# finacbv1.net
KiCad netlist of a schematic drawn in EAGLE
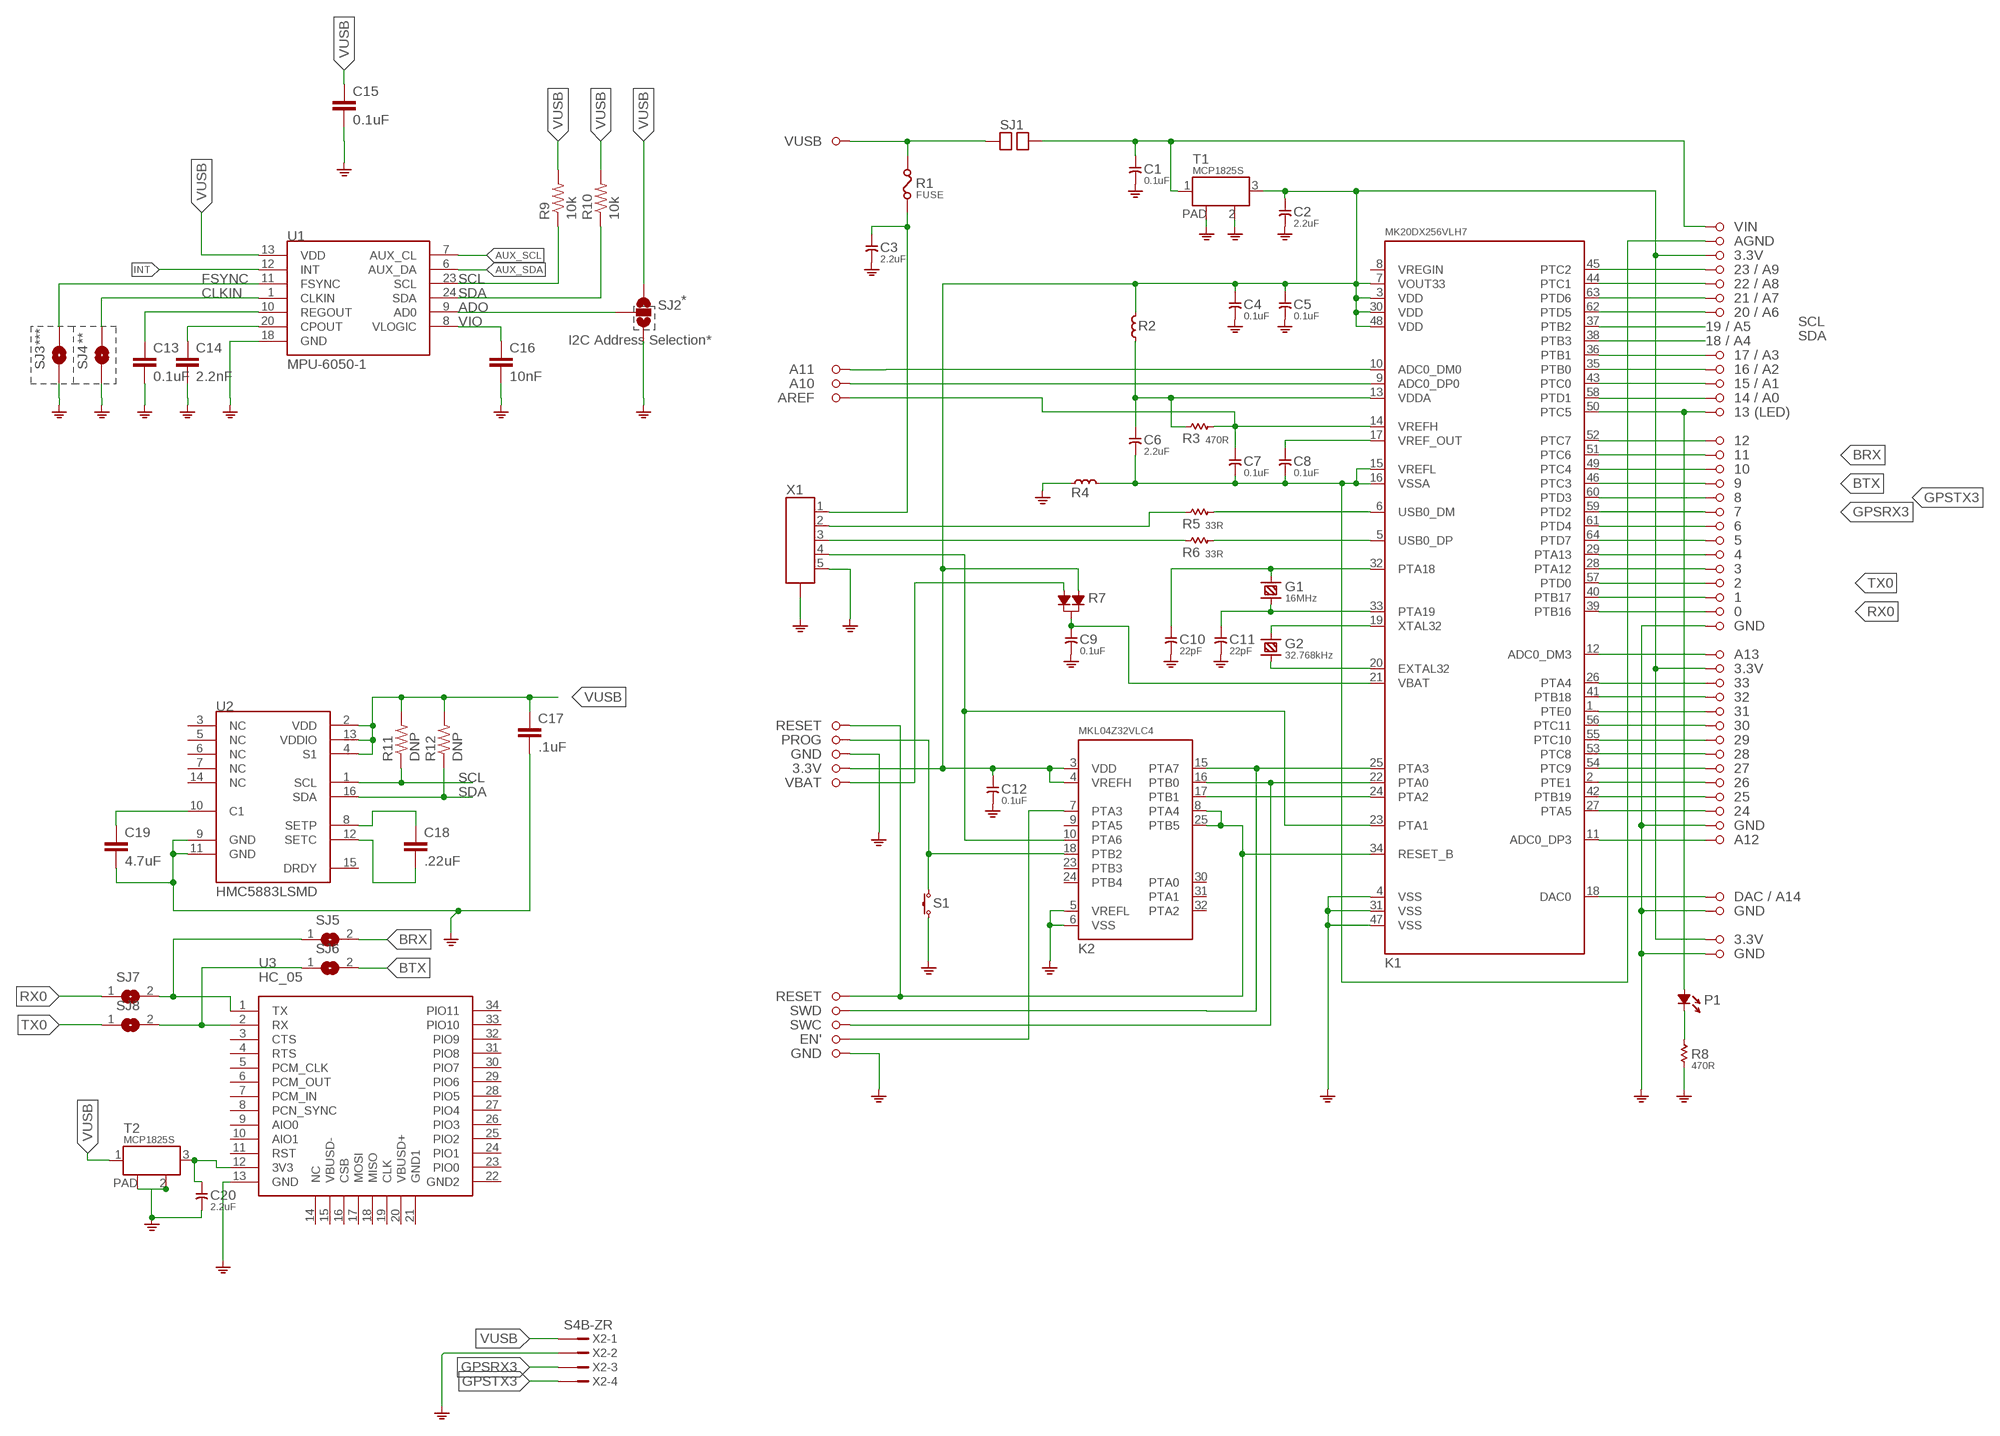
[diagram p0: schematic, sheet 1]

(export (version "E")
  (design (tool "Eeschema 10.0.6"))
  (components
    (comp (ref "C1")
      (value "0.1uF")
      (footprint "eagle-import:C0603")
      (fields (field (name "MF") "Murata Electronics") (field (name "MPN") "GRM188R71C104KA01D"))
      (libsource (lib "eagle-import") (part "CAPACITOR-0.1UF"))
    )
    (comp (ref "C2")
      (value "2.2uF")
      (footprint "eagle-import:C0805")
      (fields (field (name "MF") "Taiyo Yuden") (field (name "MPN") "TMK212B7225KG-TR"))
      (libsource (lib "eagle-import") (part "CAPACITOR-2.2UF"))
    )
    (comp (ref "C3")
      (value "2.2uF")
      (footprint "eagle-import:C0805")
      (fields (field (name "MF") "Taiyo Yuden") (field (name "MPN") "TMK212B7225KG-TR"))
      (libsource (lib "eagle-import") (part "CAPACITOR-2.2UF"))
    )
    (comp (ref "C4")
      (value "0.1uF")
      (footprint "eagle-import:C0603")
      (fields (field (name "MF") "Murata Electronics") (field (name "MPN") "GRM188R71C104KA01D"))
      (libsource (lib "eagle-import") (part "CAPACITOR-0.1UF"))
    )
    (comp (ref "C5")
      (value "0.1uF")
      (footprint "eagle-import:C0603")
      (fields (field (name "MF") "Murata Electronics") (field (name "MPN") "GRM188R71C104KA01D"))
      (libsource (lib "eagle-import") (part "CAPACITOR-0.1UF"))
    )
    (comp (ref "C6")
      (value "2.2uF")
      (footprint "eagle-import:C0805")
      (fields (field (name "MF") "Taiyo Yuden") (field (name "MPN") "TMK212B7225KG-TR"))
      (libsource (lib "eagle-import") (part "CAPACITOR-2.2UF"))
    )
    (comp (ref "C7")
      (value "0.1uF")
      (footprint "eagle-import:C0603")
      (fields (field (name "MF") "Murata Electronics") (field (name "MPN") "GRM188R71C104KA01D"))
      (libsource (lib "eagle-import") (part "CAPACITOR-0.1UF"))
    )
    (comp (ref "C8")
      (value "0.1uF")
      (footprint "eagle-import:C0603")
      (fields (field (name "MF") "Murata Electronics") (field (name "MPN") "GRM188R71C104KA01D"))
      (libsource (lib "eagle-import") (part "CAPACITOR-0.1UF"))
    )
    (comp (ref "C9")
      (value "0.1uF")
      (footprint "eagle-import:C0603")
      (fields (field (name "MF") "Murata Electronics") (field (name "MPN") "GRM188R71C104KA01D"))
      (libsource (lib "eagle-import") (part "CAPACITOR-0.1UF"))
    )
    (comp (ref "C10")
      (value "22pF")
      (footprint "eagle-import:C0603")
      (fields (field (name "MF") "Vishay / Vitramon") (field (name "MPN") "VJ0603A220JXACW1BC"))
      (libsource (lib "eagle-import") (part "CAPACITOR-22PF"))
    )
    (comp (ref "C11")
      (value "22pF")
      (footprint "eagle-import:C0603")
      (fields (field (name "MF") "Vishay / Vitramon") (field (name "MPN") "VJ0603A220JXACW1BC"))
      (libsource (lib "eagle-import") (part "CAPACITOR-22PF"))
    )
    (comp (ref "C12")
      (value "0.1uF")
      (footprint "eagle-import:C0603")
      (fields (field (name "MF") "Murata Electronics") (field (name "MPN") "GRM188R71C104KA01D"))
      (libsource (lib "eagle-import") (part "CAPACITOR-0.1UF"))
    )
    (comp (ref "C13")
      (value "0.1uF")
      (footprint "eagle-import:0603-CAP")
      (libsource (lib "eagle-import") (part "CAP0603-CAP"))
    )
    (comp (ref "C14")
      (value "2.2nF")
      (footprint "eagle-import:0603-CAP")
      (libsource (lib "eagle-import") (part "CAP0603-CAP"))
    )
    (comp (ref "C15")
      (value "0.1uF")
      (footprint "eagle-import:0603-CAP")
      (libsource (lib "eagle-import") (part "CAP0603-CAP"))
    )
    (comp (ref "C16")
      (value "10nF")
      (footprint "eagle-import:0603-CAP")
      (libsource (lib "eagle-import") (part "CAP0603-CAP"))
    )
    (comp (ref "C17")
      (value ".1uF")
      (footprint "eagle-import:0402-CAP")
      (libsource (lib "eagle-import") (part "CAP0402-CAP"))
    )
    (comp (ref "C18")
      (value ".22uF")
      (footprint "eagle-import:0402-CAP")
      (libsource (lib "eagle-import") (part "CAP0402-CAP"))
    )
    (comp (ref "C19")
      (value "4.7uF")
      (footprint "eagle-import:0402-CAP")
      (libsource (lib "eagle-import") (part "CAP0402-CAP"))
    )
    (comp (ref "C20")
      (value "2.2uF")
      (footprint "eagle-import:C0805")
      (fields (field (name "MF") "Taiyo Yuden") (field (name "MPN") "TMK212B7225KG-TR"))
      (libsource (lib "eagle-import") (part "CAPACITOR-2.2UF"))
    )
    (comp (ref "G1")
      (value "16MHz")
      (footprint "eagle-import:HC49US")
      (fields (field (name "MF") "ABRACON") (field (name "MPN") "ABL-16.000MHz-B1U"))
      (libsource (lib "eagle-import") (part "CRYSTAL-HC49US"))
    )
    (comp (ref "G2")
      (value "32.768kHz")
      (footprint "eagle-import:TC26H")
      (fields (field (name "MF") "Citizen FineDevice") (field (name "MPN") " CFS206-32.768KDZF-UB"))
      (libsource (lib "eagle-import") (part "CRYSTAL-TC26H"))
    )
    (comp (ref "K1")
      (value "MK20DX256VLH7")
      (footprint "eagle-import:LQFP64-05")
      (fields (field (name "MF") "NXP"))
      (libsource (lib "eagle-import") (part "MK20DX256VLH7"))
    )
    (comp (ref "K2")
      (value "MKL04Z32VLC4")
      (footprint "eagle-import:LQFP32-08")
      (fields (field (name "MF") "PJRC") (field (name "MPN") "IC_MKL04Z32_TQFP32"))
      (libsource (lib "eagle-import") (part "MKL04Z32VLC4"))
    )
    (comp (ref "P1")
      (value "LED")
      (footprint "eagle-import:LED-0805")
      (fields (field (name "MF") "ROHM Semiconductor") (field (name "MPN") "SML-211DTT86"))
      (libsource (lib "eagle-import") (part "LED"))
    )
    (comp (ref "R1")
      (value "FUSE")
      (footprint "eagle-import:F0805")
      (fields (field (name "MF") "Bel Fuse") (field (name "MPN") "0ZCK0050FF2E"))
      (libsource (lib "eagle-import") (part "FUSE"))
    )
    (comp (ref "R2")
      (value "FERRITE")
      (footprint "eagle-import:L0603")
      (fields (field (name "MF") "Murata Electronics") (field (name "MPN") " BLM18AG601SN1D"))
      (libsource (lib "eagle-import") (part "FERRITE"))
    )
    (comp (ref "R3")
      (value "470R")
      (footprint "eagle-import:R0603")
      (fields (field (name "MF") "Vishay") (field (name "MPN") "CRCW0603470RFKEA"))
      (libsource (lib "eagle-import") (part "RESISTOR-470R"))
    )
    (comp (ref "R4")
      (value "FERRITE")
      (footprint "eagle-import:L0603")
      (fields (field (name "MF") "Murata Electronics") (field (name "MPN") " BLM18AG601SN1D"))
      (libsource (lib "eagle-import") (part "FERRITE"))
    )
    (comp (ref "R5")
      (value "33R")
      (footprint "eagle-import:R0603")
      (fields (field (name "MF") "Panasonic") (field (name "MPN") "ERJ-PA3F33R0V"))
      (libsource (lib "eagle-import") (part "RESISTOR-33R"))
    )
    (comp (ref "R6")
      (value "33R")
      (footprint "eagle-import:R0603")
      (fields (field (name "MF") "Panasonic") (field (name "MPN") "ERJ-PA3F33R0V"))
      (libsource (lib "eagle-import") (part "RESISTOR-33R"))
    )
    (comp (ref "R7")
      (value "DIODE_DUAL")
      (footprint "eagle-import:SOT-23")
      (fields (field (name "MF") "NXP Semiconductors") (field (name "MPN") "BAT54C,215"))
      (libsource (lib "eagle-import") (part "DIODE_DUAL"))
    )
    (comp (ref "R8")
      (value "470R")
      (footprint "eagle-import:R0603")
      (fields (field (name "MF") "Vishay") (field (name "MPN") "CRCW0603470RFKEA"))
      (libsource (lib "eagle-import") (part "RESISTOR-470R"))
    )
    (comp (ref "R9")
      (value "10k")
      (footprint "eagle-import:0603-RES")
      (libsource (lib "eagle-import") (part "RESISTOR0603-RES"))
    )
    (comp (ref "R10")
      (value "10k")
      (footprint "eagle-import:0603-RES")
      (libsource (lib "eagle-import") (part "RESISTOR0603-RES"))
    )
    (comp (ref "R11")
      (value "DNP")
      (footprint "eagle-import:0402-RES")
      (libsource (lib "eagle-import") (part "RESISTOR0402-RES"))
    )
    (comp (ref "R12")
      (value "DNP")
      (footprint "eagle-import:0402-RES")
      (libsource (lib "eagle-import") (part "RESISTOR0402-RES"))
    )
    (comp (ref "S1")
      (value "TACT_SWITCH")
      (footprint "eagle-import:ALPS_SKHH")
      (fields (field (name "MF") "ALPS") (field (name "MPN") "SKHHPKA010"))
      (libsource (lib "eagle-import") (part "TACT_SWITCH"))
    )
    (comp (ref "SJ1")
      (value "SOLDERJUMPER")
      (footprint "eagle-import:SOLDERJUMPER")
      (libsource (lib "eagle-import") (part "SOLDERJUMPER"))
    )
    (comp (ref "SJ2")
      (value "SOLDERJUMPER_2WAYPASTE2&3")
      (footprint "eagle-import:SJ_3_PASTE2&3")
      (libsource (lib "eagle-import") (part "SOLDERJUMPER_2WAYPASTE2&3"))
    )
    (comp (ref "SJ3")
      (value "SOLDERJUMPERTRACE")
      (footprint "eagle-import:SJ_2S-TRACE")
      (libsource (lib "eagle-import") (part "SOLDERJUMPERTRACE"))
    )
    (comp (ref "SJ4")
      (value "SOLDERJUMPERTRACE")
      (footprint "eagle-import:SJ_2S-TRACE")
      (libsource (lib "eagle-import") (part "SOLDERJUMPERTRACE"))
    )
    (comp (ref "SJ5") (value "SJ") (footprint "eagle-import:SJ") (libsource (lib "eagle-import") (part "SJ")))
    (comp (ref "SJ6") (value "SJ") (footprint "eagle-import:SJ") (libsource (lib "eagle-import") (part "SJ")))
    (comp (ref "SJ7") (value "SJ") (footprint "eagle-import:SJ") (libsource (lib "eagle-import") (part "SJ")))
    (comp (ref "SJ8") (value "SJ") (footprint "eagle-import:SJ") (libsource (lib "eagle-import") (part "SJ")))
    (comp (ref "SX1")
      (value "PIN")
      (footprint "eagle-import:PTH_39MIL")
      (libsource (lib "eagle-import") (part "PIN"))
    )
    (comp (ref "SX2")
      (value "PIN")
      (footprint "eagle-import:PTH_39MIL")
      (libsource (lib "eagle-import") (part "PIN"))
    )
    (comp (ref "SX3")
      (value "PIN")
      (footprint "eagle-import:PTH_39MIL")
      (libsource (lib "eagle-import") (part "PIN"))
    )
    (comp (ref "SX4")
      (value "PIN")
      (footprint "eagle-import:PTH_39MIL")
      (libsource (lib "eagle-import") (part "PIN"))
    )
    (comp (ref "SX5")
      (value "PIN")
      (footprint "eagle-import:PTH_39MIL")
      (libsource (lib "eagle-import") (part "PIN"))
    )
    (comp (ref "SX6")
      (value "PIN")
      (footprint "eagle-import:PTH_39MIL")
      (libsource (lib "eagle-import") (part "PIN"))
    )
    (comp (ref "SX7")
      (value "PIN")
      (footprint "eagle-import:PTH_39MIL")
      (libsource (lib "eagle-import") (part "PIN"))
    )
    (comp (ref "SX8")
      (value "PIN")
      (footprint "eagle-import:PTH_39MIL")
      (libsource (lib "eagle-import") (part "PIN"))
    )
    (comp (ref "SX11")
      (value "PIN")
      (footprint "eagle-import:PTH_39MIL")
      (libsource (lib "eagle-import") (part "PIN"))
    )
    (comp (ref "SX12")
      (value "PIN")
      (footprint "eagle-import:PTH_39MIL")
      (libsource (lib "eagle-import") (part "PIN"))
    )
    (comp (ref "SX13")
      (value "PIN")
      (footprint "eagle-import:PTH_39MIL")
      (libsource (lib "eagle-import") (part "PIN"))
    )
    (comp (ref "SX14")
      (value "PIN")
      (footprint "eagle-import:PTH_39MIL")
      (libsource (lib "eagle-import") (part "PIN"))
    )
    (comp (ref "SX15")
      (value "PIN")
      (footprint "eagle-import:PTH_39MIL")
      (libsource (lib "eagle-import") (part "PIN"))
    )
    (comp (ref "SX16")
      (value "PIN")
      (footprint "eagle-import:PTH_39MIL")
      (libsource (lib "eagle-import") (part "PIN"))
    )
    (comp (ref "SX17")
      (value "PIN")
      (footprint "eagle-import:PTH_39MIL")
      (libsource (lib "eagle-import") (part "PIN"))
    )
    (comp (ref "SX18")
      (value "PIN")
      (footprint "eagle-import:PTH_39MIL")
      (libsource (lib "eagle-import") (part "PIN"))
    )
    (comp (ref "SX19")
      (value "PIN")
      (footprint "eagle-import:PTH_39MIL")
      (libsource (lib "eagle-import") (part "PIN"))
    )
    (comp (ref "SX20")
      (value "PIN")
      (footprint "eagle-import:PTH_39MIL")
      (libsource (lib "eagle-import") (part "PIN"))
    )
    (comp (ref "SX21")
      (value "PIN")
      (footprint "eagle-import:PTH_39MIL")
      (libsource (lib "eagle-import") (part "PIN"))
    )
    (comp (ref "SX22")
      (value "PIN")
      (footprint "eagle-import:PTH_39MIL")
      (libsource (lib "eagle-import") (part "PIN"))
    )
    (comp (ref "SX23")
      (value "PIN")
      (footprint "eagle-import:PTH_39MIL")
      (libsource (lib "eagle-import") (part "PIN"))
    )
    (comp (ref "SX24")
      (value "PIN")
      (footprint "eagle-import:PTH_39MIL")
      (libsource (lib "eagle-import") (part "PIN"))
    )
    (comp (ref "SX25")
      (value "PIN")
      (footprint "eagle-import:PTH_39MIL")
      (libsource (lib "eagle-import") (part "PIN"))
    )
    (comp (ref "SX26")
      (value "PIN")
      (footprint "eagle-import:PTH_39MIL")
      (libsource (lib "eagle-import") (part "PIN"))
    )
    (comp (ref "SX27")
      (value "PIN")
      (footprint "eagle-import:PTH_39MIL")
      (libsource (lib "eagle-import") (part "PIN"))
    )
    (comp (ref "SX28")
      (value "PIN")
      (footprint "eagle-import:PTH_39MIL")
      (libsource (lib "eagle-import") (part "PIN"))
    )
    (comp (ref "SX29")
      (value "PIN")
      (footprint "eagle-import:PTH_39MIL")
      (libsource (lib "eagle-import") (part "PIN"))
    )
    (comp (ref "SX30")
      (value "PIN")
      (footprint "eagle-import:PTH_39MIL")
      (libsource (lib "eagle-import") (part "PIN"))
    )
    (comp (ref "SX31")
      (value "PIN")
      (footprint "eagle-import:PTH_39MIL")
      (libsource (lib "eagle-import") (part "PIN"))
    )
    (comp (ref "SX32")
      (value "PIN")
      (footprint "eagle-import:PTH_39MIL")
      (libsource (lib "eagle-import") (part "PIN"))
    )
    (comp (ref "SX33")
      (value "PIN")
      (footprint "eagle-import:PTH_39MIL")
      (libsource (lib "eagle-import") (part "PIN"))
    )
    (comp (ref "SX34")
      (value "PIN")
      (footprint "eagle-import:PTH_39MIL")
      (libsource (lib "eagle-import") (part "PIN"))
    )
    (comp (ref "SX35")
      (value "PIN")
      (footprint "eagle-import:PTH_39MIL")
      (libsource (lib "eagle-import") (part "PIN"))
    )
    (comp (ref "SX36")
      (value "PIN")
      (footprint "eagle-import:PTH_39MIL")
      (libsource (lib "eagle-import") (part "PIN"))
    )
    (comp (ref "SX37")
      (value "PIN")
      (footprint "eagle-import:PTH_39MIL")
      (libsource (lib "eagle-import") (part "PIN"))
    )
    (comp (ref "SX38")
      (value "PIN")
      (footprint "eagle-import:PTH_39MIL")
      (libsource (lib "eagle-import") (part "PIN"))
    )
    (comp (ref "SX39")
      (value "PIN")
      (footprint "eagle-import:PTH_39MIL")
      (libsource (lib "eagle-import") (part "PIN"))
    )
    (comp (ref "SX40")
      (value "PIN")
      (footprint "eagle-import:PTH_39MIL")
      (libsource (lib "eagle-import") (part "PIN"))
    )
    (comp (ref "SX41")
      (value "PIN")
      (footprint "eagle-import:PTH_39MIL")
      (libsource (lib "eagle-import") (part "PIN"))
    )
    (comp (ref "SX42")
      (value "PIN")
      (footprint "eagle-import:PTH_39MIL")
      (libsource (lib "eagle-import") (part "PIN"))
    )
    (comp (ref "SX43")
      (value "PIN")
      (footprint "eagle-import:PTH_39MIL")
      (libsource (lib "eagle-import") (part "PIN"))
    )
    (comp (ref "SX44")
      (value "PIN")
      (footprint "eagle-import:PTH_39MIL")
      (libsource (lib "eagle-import") (part "PIN"))
    )
    (comp (ref "SX45")
      (value "PIN")
      (footprint "eagle-import:PTH_39MIL")
      (libsource (lib "eagle-import") (part "PIN"))
    )
    (comp (ref "SX46")
      (value "PIN")
      (footprint "eagle-import:PTH_39MIL")
      (libsource (lib "eagle-import") (part "PIN"))
    )
    (comp (ref "SX47")
      (value "PIN")
      (footprint "eagle-import:PTH_39MIL")
      (libsource (lib "eagle-import") (part "PIN"))
    )
    (comp (ref "SX48")
      (value "PIN")
      (footprint "eagle-import:PTH_39MIL")
      (libsource (lib "eagle-import") (part "PIN"))
    )
    (comp (ref "SX49")
      (value "PIN")
      (footprint "eagle-import:PTH_39MIL")
      (libsource (lib "eagle-import") (part "PIN"))
    )
    (comp (ref "SX50")
      (value "PIN")
      (footprint "eagle-import:PTH_39MIL")
      (libsource (lib "eagle-import") (part "PIN"))
    )
    (comp (ref "SX51")
      (value "PIN")
      (footprint "eagle-import:PTH_39MIL")
      (libsource (lib "eagle-import") (part "PIN"))
    )
    (comp (ref "SX52")
      (value "PIN")
      (footprint "eagle-import:PTH_39MIL")
      (libsource (lib "eagle-import") (part "PIN"))
    )
    (comp (ref "SX53")
      (value "PIN")
      (footprint "eagle-import:PTH_39MIL")
      (libsource (lib "eagle-import") (part "PIN"))
    )
    (comp (ref "SX54")
      (value "PIN")
      (footprint "eagle-import:PTH_39MIL")
      (libsource (lib "eagle-import") (part "PIN"))
    )
    (comp (ref "SX55")
      (value "PIN")
      (footprint "eagle-import:PTH_39MIL")
      (libsource (lib "eagle-import") (part "PIN"))
    )
    (comp (ref "SX56")
      (value "PIN")
      (footprint "eagle-import:PTH_39MIL")
      (libsource (lib "eagle-import") (part "PIN"))
    )
    (comp (ref "SX57")
      (value "PIN")
      (footprint "eagle-import:PTH_39MIL")
      (libsource (lib "eagle-import") (part "PIN"))
    )
    (comp (ref "SX58")
      (value "PIN")
      (footprint "eagle-import:PTH_39MIL")
      (libsource (lib "eagle-import") (part "PIN"))
    )
    (comp (ref "SX59")
      (value "PIN")
      (footprint "eagle-import:PTH_39MIL")
      (libsource (lib "eagle-import") (part "PIN"))
    )
    (comp (ref "SX60")
      (value "PIN")
      (footprint "eagle-import:PTH_39MIL")
      (libsource (lib "eagle-import") (part "PIN"))
    )
    (comp (ref "T1")
      (value "MCP1825S")
      (footprint "eagle-import:SOT-223")
      (fields (field (name "MF") "Microchip Technology") (field (name "MPN") "MCP1825S-3302E/DB"))
      (libsource (lib "eagle-import") (part "LDO"))
    )
    (comp (ref "T2")
      (value "MCP1825S")
      (footprint "eagle-import:SOT-223")
      (fields (field (name "MF") "Microchip Technology") (field (name "MPN") "MCP1825S-3302E/DB"))
      (libsource (lib "eagle-import") (part "LDO"))
    )
    (comp (ref "U1")
      (value "MPU-6050-1")
      (footprint "eagle-import:QFN-24-4MM2")
      (libsource (lib "eagle-import") (part "MPU-6050-1"))
    )
    (comp (ref "U2")
      (value "HMC5883LSMD")
      (footprint "eagle-import:16LPCC")
      (libsource (lib "eagle-import") (part "HMC5883LSMD"))
    )
    (comp (ref "U3")
      (value "HC_05")
      (footprint "eagle-import:BLUETOOTH_SMD")
      (libsource (lib "eagle-import") (part "HC_05"))
    )
    (comp (ref "X1")
      (value "MINI-USB")
      (footprint "eagle-import:MOLEX_SD-67503-010")
      (fields (field (name "MF") "MOLEX") (field (name "MPN") "0675031020"))
      (libsource (lib "eagle-import") (part "MINI-USBMOLEX_0675031230"))
    )
    (comp (ref "X2")
      (value "S4B-ZR")
      (footprint "eagle-import:S4B-ZR")
      (fields (field (name "MF") "FARNELL") (field (name "MPN") "S4B-ZR(LF)(SN)"))
      (libsource (lib "eagle-import") (part "?4B-ZRS"))
    )
  )
  (nets
    (net (code "1") (name "/ADO") (class "Default")
      (node (ref "SJ2") (pin "2") (pinfunction "2_2") (pintype "passive"))
      (node (ref "U1") (pin "9") (pinfunction "AD0_9") (pintype "bidirectional"))
    )
    (net (code "2") (name "/CLKIN") (class "Default")
      (node (ref "SJ4") (pin "2") (pinfunction "2_2") (pintype "passive"))
      (node (ref "U1") (pin "1") (pinfunction "CLKIN_1") (pintype "bidirectional"))
    )
    (net (code "3") (name "/FSYNC") (class "Default")
      (node (ref "SJ3") (pin "2") (pinfunction "2_2") (pintype "passive"))
      (node (ref "U1") (pin "11") (pinfunction "FSYNC_11") (pintype "bidirectional"))
    )
    (net (code "4") (name "/SCL") (class "Default")
      (node (ref "K1") (pin "37") (pinfunction "PTB2_37") (pintype "bidirectional"))
      (node (ref "R11") (pin "1") (pinfunction "1_1") (pintype "passive"))
      (node (ref "R9") (pin "1") (pinfunction "1_1") (pintype "passive"))
      (node (ref "U1") (pin "23") (pinfunction "SCL_23") (pintype "bidirectional"))
      (node (ref "U2") (pin "1") (pinfunction "SCL_1") (pintype "bidirectional"))
    )
    (net (code "5") (name "/SDA") (class "Default")
      (node (ref "K1") (pin "38") (pinfunction "PTB3_38") (pintype "bidirectional"))
      (node (ref "R10") (pin "1") (pinfunction "1_1") (pintype "passive"))
      (node (ref "R12") (pin "1") (pinfunction "1_1") (pintype "passive"))
      (node (ref "U1") (pin "24") (pinfunction "SDA_24") (pintype "bidirectional"))
      (node (ref "U2") (pin "16") (pinfunction "SDA_16") (pintype "bidirectional"))
    )
    (net (code "6") (name "/VIO") (class "Default")
      (node (ref "C16") (pin "1") (pinfunction "1_1") (pintype "passive"))
      (node (ref "U1") (pin "8") (pinfunction "VLOGIC_8") (pintype "bidirectional"))
    )
    (net (code "7") (name "AUX_SCL") (class "Default")
      (node (ref "U1") (pin "7") (pinfunction "AUX_CL_7") (pintype "bidirectional"))
    )
    (net (code "8") (name "AUX_SDA") (class "Default")
      (node (ref "U1") (pin "6") (pinfunction "AUX_DA_6") (pintype "bidirectional"))
    )
    (net (code "9") (name "BRX") (class "Default")
      (node (ref "K1") (pin "49") (pinfunction "PTC4_49") (pintype "bidirectional"))
      (node (ref "SJ5") (pin "2") (pinfunction "2_2") (pintype "passive"))
      (node (ref "SX21") (pin "1") (pinfunction "P$1_1") (pintype "bidirectional"))
    )
    (net (code "10") (name "BTX") (class "Default")
      (node (ref "K1") (pin "46") (pinfunction "PTC3_46") (pintype "bidirectional"))
      (node (ref "SJ6") (pin "2") (pinfunction "2_2") (pintype "passive"))
      (node (ref "SX22") (pin "1") (pinfunction "P$1_1") (pintype "bidirectional"))
    )
    (net (code "11") (name "GND") (class "Default")
      (node (ref "C1") (pin "2") (pinfunction "2_2") (pintype "passive"))
      (node (ref "C10") (pin "2") (pinfunction "2_2") (pintype "passive"))
      (node (ref "C11") (pin "2") (pinfunction "2_2") (pintype "passive"))
      (node (ref "C12") (pin "2") (pinfunction "2_2") (pintype "passive"))
      (node (ref "C13") (pin "2") (pinfunction "2_2") (pintype "passive"))
      (node (ref "C14") (pin "2") (pinfunction "2_2") (pintype "passive"))
      (node (ref "C15") (pin "2") (pinfunction "2_2") (pintype "passive"))
      (node (ref "C16") (pin "2") (pinfunction "2_2") (pintype "passive"))
      (node (ref "C17") (pin "2") (pinfunction "2_2") (pintype "passive"))
      (node (ref "C19") (pin "2") (pinfunction "2_2") (pintype "passive"))
      (node (ref "C2") (pin "2") (pinfunction "2_2") (pintype "passive"))
      (node (ref "C20") (pin "2") (pinfunction "2_2") (pintype "passive"))
      (node (ref "C3") (pin "2") (pinfunction "2_2") (pintype "passive"))
      (node (ref "C4") (pin "2") (pinfunction "2_2") (pintype "passive"))
      (node (ref "C5") (pin "2") (pinfunction "2_2") (pintype "passive"))
      (node (ref "C9") (pin "2") (pinfunction "2_2") (pintype "passive"))
      (node (ref "K1") (pin "31") (pinfunction "VSS_31") (pintype "bidirectional"))
      (node (ref "K1") (pin "4") (pinfunction "VSS_4") (pintype "bidirectional"))
      (node (ref "K1") (pin "47") (pinfunction "VSS_47") (pintype "bidirectional"))
      (node (ref "K2") (pin "5") (pinfunction "VREFL_5") (pintype "bidirectional"))
      (node (ref "K2") (pin "6") (pinfunction "VSS_6") (pintype "bidirectional"))
      (node (ref "R4") (pin "1") (pinfunction "1_1") (pintype "passive"))
      (node (ref "R8") (pin "1") (pinfunction "1_1") (pintype "passive"))
      (node (ref "S1") (pin "3") (pinfunction "3_3") (pintype "passive"))
      (node (ref "S1") (pin "4") (pinfunction "3_4") (pintype "passive"))
      (node (ref "SJ2") (pin "3") (pinfunction "3_3") (pintype "passive"))
      (node (ref "SJ3") (pin "1") (pinfunction "1_1") (pintype "passive"))
      (node (ref "SJ4") (pin "1") (pinfunction "1_1") (pintype "passive"))
      (node (ref "SX32") (pin "1") (pinfunction "P$1_1") (pintype "bidirectional"))
      (node (ref "SX42") (pin "1") (pinfunction "P$1_1") (pintype "bidirectional"))
      (node (ref "SX50") (pin "1") (pinfunction "P$1_1") (pintype "bidirectional"))
      (node (ref "SX53") (pin "1") (pinfunction "P$1_1") (pintype "bidirectional"))
      (node (ref "SX55") (pin "1") (pinfunction "P$1_1") (pintype "bidirectional"))
      (node (ref "SX60") (pin "1") (pinfunction "P$1_1") (pintype "bidirectional"))
      (node (ref "T1") (pin "2") (pinfunction "GND_2") (pintype "bidirectional"))
      (node (ref "T1") (pin "PAD") (pinfunction "PAD_PAD") (pintype "bidirectional"))
      (node (ref "T2") (pin "2") (pinfunction "GND_2") (pintype "bidirectional"))
      (node (ref "T2") (pin "PAD") (pinfunction "PAD_PAD") (pintype "bidirectional"))
      (node (ref "U1") (pin "18") (pinfunction "GND_18") (pintype "bidirectional"))
      (node (ref "U2") (pin "11") (pinfunction "GND_11") (pintype "bidirectional"))
      (node (ref "U2") (pin "9") (pinfunction "GND_9") (pintype "bidirectional"))
      (node (ref "U3") (pin "13") (pinfunction "GND_13") (pintype "bidirectional"))
      (node (ref "X1") (pin "5") (pinfunction "5_5") (pintype "input"))
      (node (ref "X1") (pin "P$1") (pinfunction "CASE_P$1") (pintype "input"))
      (node (ref "X1") (pin "P$2") (pinfunction "CASE_P$2") (pintype "input"))
      (node (ref "X1") (pin "P$3") (pinfunction "CASE_P$3") (pintype "input"))
      (node (ref "X1") (pin "P$4") (pinfunction "CASE_P$4") (pintype "input"))
      (node (ref "X1") (pin "P$5") (pinfunction "CASE_P$5") (pintype "input"))
      (node (ref "X1") (pin "P$6") (pinfunction "CASE_P$6") (pintype "input"))
      (node (ref "X2") (pin "2") (pinfunction "1_2") (pintype "passive"))
    )
    (net (code "12") (name "GPSRX3") (class "Default")
      (node (ref "K1") (pin "59") (pinfunction "PTD2_59") (pintype "bidirectional"))
      (node (ref "SX24") (pin "1") (pinfunction "P$1_1") (pintype "bidirectional"))
      (node (ref "X2") (pin "3") (pinfunction "1_3") (pintype "passive"))
    )
    (net (code "13") (name "GPSTX3") (class "Default")
      (node (ref "K1") (pin "60") (pinfunction "PTD3_60") (pintype "bidirectional"))
      (node (ref "SX23") (pin "1") (pinfunction "P$1_1") (pintype "bidirectional"))
      (node (ref "X2") (pin "4") (pinfunction "1_4") (pintype "passive"))
    )
    (net (code "14") (name "INT") (class "Default")
      (node (ref "U1") (pin "12") (pinfunction "INT_12") (pintype "bidirectional"))
    )
    (net (code "15") (name "Net-(C3-Pad1)") (class "Default")
      (node (ref "C3") (pin "1") (pinfunction "1_1") (pintype "passive"))
      (node (ref "R1") (pin "1") (pinfunction "1_1") (pintype "bidirectional"))
      (node (ref "X1") (pin "1") (pinfunction "1_1") (pintype "input"))
    )
    (net (code "16") (name "Net-(G2-1)") (class "Default")
      (node (ref "G2") (pin "2") (pinfunction "1_2") (pintype "passive"))
      (node (ref "K1") (pin "19") (pinfunction "XTAL32_19") (pintype "bidirectional"))
    )
    (net (code "17") (name "Net-(G2-2)") (class "Default")
      (node (ref "G2") (pin "1") (pinfunction "2_1") (pintype "passive"))
      (node (ref "K1") (pin "20") (pinfunction "EXTAL32_20") (pintype "bidirectional"))
    )
    (net (code "18") (name "Net-(K1-ADC0_DM0)") (class "Default")
      (node (ref "K1") (pin "10") (pinfunction "ADC0_DM0_10") (pintype "bidirectional"))
      (node (ref "SX12") (pin "1") (pinfunction "P$1_1") (pintype "bidirectional"))
    )
    (net (code "19") (name "Net-(K1-ADC0_DM3)") (class "Default")
      (node (ref "K1") (pin "12") (pinfunction "ADC0_DM3_12") (pintype "bidirectional"))
      (node (ref "SX33") (pin "1") (pinfunction "P$1_1") (pintype "bidirectional"))
    )
    (net (code "20") (name "Net-(K1-ADC0_DP0)") (class "Default")
      (node (ref "K1") (pin "9") (pinfunction "ADC0_DP0_9") (pintype "bidirectional"))
      (node (ref "SX14") (pin "1") (pinfunction "P$1_1") (pintype "bidirectional"))
    )
    (net (code "21") (name "Net-(K1-ADC0_DP3)") (class "Default")
      (node (ref "K1") (pin "11") (pinfunction "ADC0_DP3_11") (pintype "bidirectional"))
      (node (ref "SX51") (pin "1") (pinfunction "P$1_1") (pintype "bidirectional"))
    )
    (net (code "22") (name "Net-(K1-DAC0)") (class "Default")
      (node (ref "K1") (pin "18") (pinfunction "DAC0_18") (pintype "bidirectional"))
      (node (ref "SX52") (pin "1") (pinfunction "P$1_1") (pintype "bidirectional"))
    )
    (net (code "23") (name "Net-(K1-PTA0)") (class "Default")
      (node (ref "K1") (pin "22") (pinfunction "PTA0_22") (pintype "bidirectional"))
      (node (ref "K2") (pin "16") (pinfunction "PTB0_16") (pintype "bidirectional"))
      (node (ref "SX58") (pin "1") (pinfunction "P$1_1") (pintype "bidirectional"))
    )
    (net (code "24") (name "Net-(K1-PTA1)") (class "Default")
      (node (ref "K1") (pin "23") (pinfunction "PTA1_23") (pintype "bidirectional"))
      (node (ref "K2") (pin "10") (pinfunction "PTA6_10") (pintype "bidirectional"))
      (node (ref "X1") (pin "4") (pinfunction "4_4") (pintype "input"))
    )
    (net (code "25") (name "Net-(K1-PTA2)") (class "Default")
      (node (ref "K1") (pin "24") (pinfunction "PTA2_24") (pintype "bidirectional"))
      (node (ref "K2") (pin "17") (pinfunction "PTB1_17") (pintype "bidirectional"))
    )
    (net (code "26") (name "Net-(K1-PTA3)") (class "Default")
      (node (ref "K1") (pin "25") (pinfunction "PTA3_25") (pintype "bidirectional"))
      (node (ref "K2") (pin "15") (pinfunction "PTA7_15") (pintype "bidirectional"))
      (node (ref "SX57") (pin "1") (pinfunction "P$1_1") (pintype "bidirectional"))
    )
    (net (code "27") (name "Net-(K1-PTA4)") (class "Default")
      (node (ref "K1") (pin "26") (pinfunction "PTA4_26") (pintype "bidirectional"))
      (node (ref "SX35") (pin "1") (pinfunction "P$1_1") (pintype "bidirectional"))
    )
    (net (code "28") (name "Net-(K1-PTA5)") (class "Default")
      (node (ref "K1") (pin "27") (pinfunction "PTA5_27") (pintype "bidirectional"))
      (node (ref "SX49") (pin "1") (pinfunction "P$1_1") (pintype "bidirectional"))
    )
    (net (code "29") (name "Net-(K1-PTA12)") (class "Default")
      (node (ref "K1") (pin "28") (pinfunction "PTA12_28") (pintype "bidirectional"))
      (node (ref "SX28") (pin "1") (pinfunction "P$1_1") (pintype "bidirectional"))
    )
    (net (code "30") (name "Net-(K1-PTA13)") (class "Default")
      (node (ref "K1") (pin "29") (pinfunction "PTA13_29") (pintype "bidirectional"))
      (node (ref "SX27") (pin "1") (pinfunction "P$1_1") (pintype "bidirectional"))
    )
    (net (code "31") (name "Net-(K1-PTA18)") (class "Default")
      (node (ref "C10") (pin "1") (pinfunction "1_1") (pintype "passive"))
      (node (ref "G1") (pin "1") (pinfunction "1_1") (pintype "passive"))
      (node (ref "K1") (pin "32") (pinfunction "PTA18_32") (pintype "bidirectional"))
    )
    (net (code "32") (name "Net-(K1-PTA19)") (class "Default")
      (node (ref "C11") (pin "1") (pinfunction "1_1") (pintype "passive"))
      (node (ref "G1") (pin "2") (pinfunction "2_2") (pintype "passive"))
      (node (ref "K1") (pin "33") (pinfunction "PTA19_33") (pintype "bidirectional"))
    )
    (net (code "33") (name "Net-(K1-PTB0)") (class "Default")
      (node (ref "K1") (pin "35") (pinfunction "PTB0_35") (pintype "bidirectional"))
      (node (ref "SX13") (pin "1") (pinfunction "P$1_1") (pintype "bidirectional"))
    )
    (net (code "34") (name "Net-(K1-PTB1)") (class "Default")
      (node (ref "K1") (pin "36") (pinfunction "PTB1_36") (pintype "bidirectional"))
      (node (ref "SX11") (pin "1") (pinfunction "P$1_1") (pintype "bidirectional"))
    )
    (net (code "35") (name "Net-(K1-PTB18)") (class "Default")
      (node (ref "K1") (pin "41") (pinfunction "PTB18_41") (pintype "bidirectional"))
      (node (ref "SX36") (pin "1") (pinfunction "P$1_1") (pintype "bidirectional"))
    )
    (net (code "36") (name "Net-(K1-PTB19)") (class "Default")
      (node (ref "K1") (pin "42") (pinfunction "PTB19_42") (pintype "bidirectional"))
      (node (ref "SX48") (pin "1") (pinfunction "P$1_1") (pintype "bidirectional"))
    )
    (net (code "37") (name "Net-(K1-PTC0)") (class "Default")
      (node (ref "K1") (pin "43") (pinfunction "PTC0_43") (pintype "bidirectional"))
      (node (ref "SX15") (pin "1") (pinfunction "P$1_1") (pintype "bidirectional"))
    )
    (net (code "38") (name "Net-(K1-PTC1)") (class "Default")
      (node (ref "K1") (pin "44") (pinfunction "PTC1_44") (pintype "bidirectional"))
      (node (ref "SX6") (pin "1") (pinfunction "P$1_1") (pintype "bidirectional"))
    )
    (net (code "39") (name "Net-(K1-PTC2)") (class "Default")
      (node (ref "K1") (pin "45") (pinfunction "PTC2_45") (pintype "bidirectional"))
      (node (ref "SX5") (pin "1") (pinfunction "P$1_1") (pintype "bidirectional"))
    )
    (net (code "40") (name "Net-(K1-PTC5)") (class "Default")
      (node (ref "K1") (pin "50") (pinfunction "PTC5_50") (pintype "bidirectional"))
      (node (ref "P1") (pin "+") (pinfunction "+_+") (pintype "passive"))
      (node (ref "SX18") (pin "1") (pinfunction "P$1_1") (pintype "bidirectional"))
    )
    (net (code "41") (name "Net-(K1-PTC6)") (class "Default")
      (node (ref "K1") (pin "51") (pinfunction "PTC6_51") (pintype "bidirectional"))
      (node (ref "SX20") (pin "1") (pinfunction "P$1_1") (pintype "bidirectional"))
    )
    (net (code "42") (name "Net-(K1-PTC7)") (class "Default")
      (node (ref "K1") (pin "52") (pinfunction "PTC7_52") (pintype "bidirectional"))
      (node (ref "SX19") (pin "1") (pinfunction "P$1_1") (pintype "bidirectional"))
    )
    (net (code "43") (name "Net-(K1-PTC8)") (class "Default")
      (node (ref "K1") (pin "53") (pinfunction "PTC8_53") (pintype "bidirectional"))
      (node (ref "SX43") (pin "1") (pinfunction "P$1_1") (pintype "bidirectional"))
    )
    (net (code "44") (name "Net-(K1-PTC9)") (class "Default")
      (node (ref "K1") (pin "54") (pinfunction "PTC9_54") (pintype "bidirectional"))
      (node (ref "SX45") (pin "1") (pinfunction "P$1_1") (pintype "bidirectional"))
    )
    (net (code "45") (name "Net-(K1-PTC10)") (class "Default")
      (node (ref "K1") (pin "55") (pinfunction "PTC10_55") (pintype "bidirectional"))
      (node (ref "SX41") (pin "1") (pinfunction "P$1_1") (pintype "bidirectional"))
    )
    (net (code "46") (name "Net-(K1-PTC11)") (class "Default")
      (node (ref "K1") (pin "56") (pinfunction "PTC11_56") (pintype "bidirectional"))
      (node (ref "SX39") (pin "1") (pinfunction "P$1_1") (pintype "bidirectional"))
    )
    (net (code "47") (name "Net-(K1-PTD0)") (class "Default")
      (node (ref "K1") (pin "57") (pinfunction "PTD0_57") (pintype "bidirectional"))
      (node (ref "SX29") (pin "1") (pinfunction "P$1_1") (pintype "bidirectional"))
    )
    (net (code "48") (name "Net-(K1-PTD1)") (class "Default")
      (node (ref "K1") (pin "58") (pinfunction "PTD1_58") (pintype "bidirectional"))
      (node (ref "SX17") (pin "1") (pinfunction "P$1_1") (pintype "bidirectional"))
    )
    (net (code "49") (name "Net-(K1-PTD4)") (class "Default")
      (node (ref "K1") (pin "61") (pinfunction "PTD4_61") (pintype "bidirectional"))
      (node (ref "SX25") (pin "1") (pinfunction "P$1_1") (pintype "bidirectional"))
    )
    (net (code "50") (name "Net-(K1-PTD5)") (class "Default")
      (node (ref "K1") (pin "62") (pinfunction "PTD5_62") (pintype "bidirectional"))
      (node (ref "SX8") (pin "1") (pinfunction "P$1_1") (pintype "bidirectional"))
    )
    (net (code "51") (name "Net-(K1-PTD6)") (class "Default")
      (node (ref "K1") (pin "63") (pinfunction "PTD6_63") (pintype "bidirectional"))
      (node (ref "SX7") (pin "1") (pinfunction "P$1_1") (pintype "bidirectional"))
    )
    (net (code "52") (name "Net-(K1-PTD7)") (class "Default")
      (node (ref "K1") (pin "64") (pinfunction "PTD7_64") (pintype "bidirectional"))
      (node (ref "SX26") (pin "1") (pinfunction "P$1_1") (pintype "bidirectional"))
    )
    (net (code "53") (name "Net-(K1-PTE0)") (class "Default")
      (node (ref "K1") (pin "1") (pinfunction "PTE0_1") (pintype "bidirectional"))
      (node (ref "SX37") (pin "1") (pinfunction "P$1_1") (pintype "bidirectional"))
    )
    (net (code "54") (name "Net-(K1-PTE1)") (class "Default")
      (node (ref "K1") (pin "2") (pinfunction "PTE1_2") (pintype "bidirectional"))
      (node (ref "SX47") (pin "1") (pinfunction "P$1_1") (pintype "bidirectional"))
    )
    (net (code "55") (name "Net-(K1-RESET_B)") (class "Default")
      (node (ref "K1") (pin "34") (pinfunction "RESET_B_34") (pintype "bidirectional"))
      (node (ref "K2") (pin "25") (pinfunction "PTB5_25") (pintype "bidirectional"))
      (node (ref "K2") (pin "8") (pinfunction "PTA4_8") (pintype "bidirectional"))
      (node (ref "SX38") (pin "1") (pinfunction "P$1_1") (pintype "bidirectional"))
      (node (ref "SX56") (pin "1") (pinfunction "P$1_1") (pintype "bidirectional"))
    )
    (net (code "56") (name "Net-(K1-USB0_DM)") (class "Default")
      (node (ref "K1") (pin "6") (pinfunction "USB0_DM_6") (pintype "bidirectional"))
      (node (ref "R5") (pin "2") (pinfunction "2_2") (pintype "passive"))
    )
    (net (code "57") (name "Net-(K1-USB0_DP)") (class "Default")
      (node (ref "K1") (pin "5") (pinfunction "USB0_DP_5") (pintype "bidirectional"))
      (node (ref "R6") (pin "2") (pinfunction "2_2") (pintype "passive"))
    )
    (net (code "58") (name "Net-(K1-VBAT)") (class "Default")
      (node (ref "C9") (pin "1") (pinfunction "1_1") (pintype "passive"))
      (node (ref "K1") (pin "21") (pinfunction "VBAT_21") (pintype "bidirectional"))
      (node (ref "R7") (pin "3") (pinfunction "3_3") (pintype "bidirectional"))
    )
    (net (code "59") (name "Net-(K1-VDDA)") (class "Default")
      (node (ref "C6") (pin "1") (pinfunction "1_1") (pintype "passive"))
      (node (ref "K1") (pin "13") (pinfunction "VDDA_13") (pintype "bidirectional"))
      (node (ref "R2") (pin "1") (pinfunction "1_1") (pintype "passive"))
      (node (ref "R3") (pin "1") (pinfunction "1_1") (pintype "passive"))
    )
    (net (code "60") (name "Net-(K1-VOUT33)") (class "Default")
      (node (ref "C12") (pin "1") (pinfunction "1_1") (pintype "passive"))
      (node (ref "C2") (pin "1") (pinfunction "1_1") (pintype "passive"))
      (node (ref "C4") (pin "1") (pinfunction "1_1") (pintype "passive"))
      (node (ref "C5") (pin "1") (pinfunction "1_1") (pintype "passive"))
      (node (ref "K1") (pin "3") (pinfunction "VDD_3") (pintype "bidirectional"))
      (node (ref "K1") (pin "30") (pinfunction "VDD_30") (pintype "bidirectional"))
      (node (ref "K1") (pin "48") (pinfunction "VDD_48") (pintype "bidirectional"))
      (node (ref "K1") (pin "7") (pinfunction "VOUT33_7") (pintype "bidirectional"))
      (node (ref "K2") (pin "3") (pinfunction "VDD_3") (pintype "bidirectional"))
      (node (ref "K2") (pin "4") (pinfunction "VREFH_4") (pintype "bidirectional"))
      (node (ref "R2") (pin "2") (pinfunction "2_2") (pintype "passive"))
      (node (ref "R7") (pin "1") (pinfunction "1_1") (pintype "bidirectional"))
      (node (ref "SX34") (pin "1") (pinfunction "P$1_1") (pintype "bidirectional"))
      (node (ref "SX4") (pin "1") (pinfunction "P$1_1") (pintype "bidirectional"))
      (node (ref "SX44") (pin "1") (pinfunction "P$1_1") (pintype "bidirectional"))
      (node (ref "SX54") (pin "1") (pinfunction "P$1_1") (pintype "bidirectional"))
      (node (ref "T1") (pin "3") (pinfunction "OUT_3") (pintype "bidirectional"))
    )
    (net (code "61") (name "Net-(K1-VREFH)") (class "Default")
      (node (ref "C7") (pin "1") (pinfunction "1_1") (pintype "passive"))
      (node (ref "K1") (pin "14") (pinfunction "VREFH_14") (pintype "bidirectional"))
      (node (ref "R3") (pin "2") (pinfunction "2_2") (pintype "passive"))
      (node (ref "SX16") (pin "1") (pinfunction "P$1_1") (pintype "bidirectional"))
    )
    (net (code "62") (name "Net-(K1-VREFL)") (class "Default")
      (node (ref "C6") (pin "2") (pinfunction "2_2") (pintype "passive"))
      (node (ref "C7") (pin "2") (pinfunction "2_2") (pintype "passive"))
      (node (ref "C8") (pin "2") (pinfunction "2_2") (pintype "passive"))
      (node (ref "K1") (pin "15") (pinfunction "VREFL_15") (pintype "bidirectional"))
      (node (ref "K1") (pin "16") (pinfunction "VSSA_16") (pintype "bidirectional"))
      (node (ref "R4") (pin "2") (pinfunction "2_2") (pintype "passive"))
      (node (ref "SX3") (pin "1") (pinfunction "P$1_1") (pintype "bidirectional"))
    )
    (net (code "63") (name "Net-(K1-VREF_OUT)") (class "Default")
      (node (ref "C8") (pin "1") (pinfunction "1_1") (pintype "passive"))
      (node (ref "K1") (pin "17") (pinfunction "VREF_OUT_17") (pintype "bidirectional"))
    )
    (net (code "64") (name "Net-(K2-PTA3)") (class "Default")
      (node (ref "K2") (pin "7") (pinfunction "PTA3_7") (pintype "bidirectional"))
      (node (ref "SX59") (pin "1") (pinfunction "P$1_1") (pintype "bidirectional"))
    )
    (net (code "65") (name "Net-(K2-PTB2)") (class "Default")
      (node (ref "K2") (pin "18") (pinfunction "PTB2_18") (pintype "bidirectional"))
      (node (ref "S1") (pin "1") (pinfunction "1_1") (pintype "passive"))
      (node (ref "S1") (pin "2") (pinfunction "1_2") (pintype "passive"))
      (node (ref "SX40") (pin "1") (pinfunction "P$1_1") (pintype "bidirectional"))
    )
    (net (code "66") (name "Net-(P1-Pad-)") (class "Default")
      (node (ref "P1") (pin "-") (pinfunction "-_-") (pintype "passive"))
      (node (ref "R8") (pin "2") (pinfunction "2_2") (pintype "passive"))
    )
    (net (code "67") (name "Net-(R5-Pad1)") (class "Default")
      (node (ref "R5") (pin "1") (pinfunction "1_1") (pintype "passive"))
      (node (ref "X1") (pin "2") (pinfunction "2_2") (pintype "input"))
    )
    (net (code "68") (name "Net-(R6-Pad1)") (class "Default")
      (node (ref "R6") (pin "1") (pinfunction "1_1") (pintype "passive"))
      (node (ref "X1") (pin "3") (pinfunction "3_3") (pintype "input"))
    )
    (net (code "69") (name "Net-(SX1-P$1)") (class "Default")
      (node (ref "R1") (pin "2") (pinfunction "2_2") (pintype "bidirectional"))
      (node (ref "SJ1") (pin "1") (pinfunction "1_1") (pintype "passive"))
      (node (ref "SX1") (pin "1") (pinfunction "P$1_1") (pintype "bidirectional"))
    )
    (net (code "70") (name "Net-(SX2-P$1)") (class "Default")
      (node (ref "C1") (pin "1") (pinfunction "1_1") (pintype "passive"))
      (node (ref "SJ1") (pin "2") (pinfunction "2_2") (pintype "passive"))
      (node (ref "SX2") (pin "1") (pinfunction "P$1_1") (pintype "bidirectional"))
      (node (ref "T1") (pin "1") (pinfunction "IN_1") (pintype "bidirectional"))
    )
    (net (code "71") (name "Net-(SX46-P$1)") (class "Default")
      (node (ref "R7") (pin "2") (pinfunction "2_2") (pintype "bidirectional"))
      (node (ref "SX46") (pin "1") (pinfunction "P$1_1") (pintype "bidirectional"))
    )
    (net (code "72") (name "Net-(T2-OUT)") (class "Default")
      (node (ref "C20") (pin "1") (pinfunction "1_1") (pintype "passive"))
      (node (ref "T2") (pin "3") (pinfunction "OUT_3") (pintype "bidirectional"))
      (node (ref "U3") (pin "12") (pinfunction "3V3_12") (pintype "bidirectional"))
    )
    (net (code "73") (name "Net-(U1-CPOUT)") (class "Default")
      (node (ref "C14") (pin "1") (pinfunction "1_1") (pintype "passive"))
      (node (ref "U1") (pin "20") (pinfunction "CPOUT_20") (pintype "bidirectional"))
    )
    (net (code "74") (name "Net-(U1-REGOUT)") (class "Default")
      (node (ref "C13") (pin "1") (pinfunction "1_1") (pintype "passive"))
      (node (ref "U1") (pin "10") (pinfunction "REGOUT_10") (pintype "bidirectional"))
    )
    (net (code "75") (name "Net-(U2-C1)") (class "Default")
      (node (ref "C19") (pin "1") (pinfunction "1_1") (pintype "passive"))
      (node (ref "U2") (pin "10") (pinfunction "C1_10") (pintype "bidirectional"))
    )
    (net (code "76") (name "Net-(U2-SETC)") (class "Default")
      (node (ref "C18") (pin "2") (pinfunction "2_2") (pintype "passive"))
      (node (ref "U2") (pin "12") (pinfunction "SETC_12") (pintype "bidirectional"))
    )
    (net (code "77") (name "Net-(U2-SETP)") (class "Default")
      (node (ref "C18") (pin "1") (pinfunction "1_1") (pintype "passive"))
      (node (ref "U2") (pin "8") (pinfunction "SETP_8") (pintype "bidirectional"))
    )
    (net (code "78") (name "Net-(U3-RX)") (class "Default")
      (node (ref "SJ6") (pin "1") (pinfunction "1_1") (pintype "passive"))
      (node (ref "SJ8") (pin "2") (pinfunction "2_2") (pintype "passive"))
      (node (ref "U3") (pin "2") (pinfunction "RX_2") (pintype "bidirectional"))
    )
    (net (code "79") (name "Net-(U3-TX)") (class "Default")
      (node (ref "SJ5") (pin "1") (pinfunction "1_1") (pintype "passive"))
      (node (ref "SJ7") (pin "2") (pinfunction "2_2") (pintype "passive"))
      (node (ref "U3") (pin "1") (pinfunction "TX_1") (pintype "bidirectional"))
    )
    (net (code "80") (name "RX0") (class "Default")
      (node (ref "K1") (pin "39") (pinfunction "PTB16_39") (pintype "bidirectional"))
      (node (ref "SJ7") (pin "1") (pinfunction "1_1") (pintype "passive"))
      (node (ref "SX31") (pin "1") (pinfunction "P$1_1") (pintype "bidirectional"))
    )
    (net (code "81") (name "TX0") (class "Default")
      (node (ref "K1") (pin "40") (pinfunction "PTB17_40") (pintype "bidirectional"))
      (node (ref "SJ8") (pin "1") (pinfunction "1_1") (pintype "passive"))
      (node (ref "SX30") (pin "1") (pinfunction "P$1_1") (pintype "bidirectional"))
    )
    (net (code "82") (name "VUSB") (class "Default")
      (node (ref "C15") (pin "1") (pinfunction "1_1") (pintype "passive"))
      (node (ref "C17") (pin "1") (pinfunction "1_1") (pintype "passive"))
      (node (ref "R10") (pin "2") (pinfunction "2_2") (pintype "passive"))
      (node (ref "R11") (pin "2") (pinfunction "2_2") (pintype "passive"))
      (node (ref "R12") (pin "2") (pinfunction "2_2") (pintype "passive"))
      (node (ref "R9") (pin "2") (pinfunction "2_2") (pintype "passive"))
      (node (ref "SJ2") (pin "1") (pinfunction "1_1") (pintype "passive"))
      (node (ref "T2") (pin "1") (pinfunction "IN_1") (pintype "bidirectional"))
      (node (ref "U1") (pin "13") (pinfunction "VDD_13") (pintype "bidirectional"))
      (node (ref "U2") (pin "13") (pinfunction "VDDIO_13") (pintype "bidirectional"))
      (node (ref "U2") (pin "2") (pinfunction "VDD_2") (pintype "bidirectional"))
      (node (ref "U2") (pin "4") (pinfunction "S1_4") (pintype "bidirectional"))
      (node (ref "X2") (pin "1") (pinfunction "1_1") (pintype "passive"))
    )
    (net (code "83") (name "unconnected-(K1-VREGIN-Pad8)") (class "Default")
      (node (ref "K1") (pin "8") (pinfunction "VREGIN_8") (pintype "bidirectional"))
    )
    (net (code "84") (name "unconnected-(K2-PTA0-Pad30)") (class "Default")
      (node (ref "K2") (pin "30") (pinfunction "PTA0_30") (pintype "bidirectional"))
    )
    (net (code "85") (name "unconnected-(K2-PTA1-Pad31)") (class "Default")
      (node (ref "K2") (pin "31") (pinfunction "PTA1_31") (pintype "bidirectional"))
    )
    (net (code "86") (name "unconnected-(K2-PTA2-Pad32)") (class "Default")
      (node (ref "K2") (pin "32") (pinfunction "PTA2_32") (pintype "bidirectional"))
    )
    (net (code "87") (name "unconnected-(K2-PTA5-Pad9)") (class "Default")
      (node (ref "K2") (pin "9") (pinfunction "PTA5_9") (pintype "bidirectional"))
    )
    (net (code "88") (name "unconnected-(K2-PTB3-Pad23)") (class "Default")
      (node (ref "K2") (pin "23") (pinfunction "PTB3_23") (pintype "bidirectional"))
    )
    (net (code "89") (name "unconnected-(K2-PTB4-Pad24)") (class "Default")
      (node (ref "K2") (pin "24") (pinfunction "PTB4_24") (pintype "bidirectional"))
    )
    (net (code "90") (name "unconnected-(U2-DRDY-Pad15)") (class "Default")
      (node (ref "U2") (pin "15") (pinfunction "DRDY_15") (pintype "bidirectional"))
    )
    (net (code "91") (name "unconnected-(U2-NC-Pad3)") (class "Default")
      (node (ref "U2") (pin "3") (pinfunction "NC_3") (pintype "bidirectional"))
    )
    (net (code "92") (name "unconnected-(U2-NC-Pad5)") (class "Default")
      (node (ref "U2") (pin "5") (pinfunction "NC_5") (pintype "bidirectional"))
    )
    (net (code "93") (name "unconnected-(U2-NC-Pad6)") (class "Default")
      (node (ref "U2") (pin "6") (pinfunction "NC_6") (pintype "bidirectional"))
    )
    (net (code "94") (name "unconnected-(U2-NC-Pad7)") (class "Default")
      (node (ref "U2") (pin "7") (pinfunction "NC_7") (pintype "bidirectional"))
    )
    (net (code "95") (name "unconnected-(U2-NC-Pad14)") (class "Default")
      (node (ref "U2") (pin "14") (pinfunction "NC_14") (pintype "bidirectional"))
    )
    (net (code "96") (name "unconnected-(U3-AIO0-Pad9)") (class "Default")
      (node (ref "U3") (pin "9") (pinfunction "AIO0_9") (pintype "bidirectional"))
    )
    (net (code "97") (name "unconnected-(U3-AIO1-Pad10)") (class "Default")
      (node (ref "U3") (pin "10") (pinfunction "AIO1_10") (pintype "bidirectional"))
    )
    (net (code "98") (name "unconnected-(U3-CLK-Pad19)") (class "Default")
      (node (ref "U3") (pin "19") (pinfunction "CLK_19") (pintype "bidirectional"))
    )
    (net (code "99") (name "unconnected-(U3-CSB-Pad16)") (class "Default")
      (node (ref "U3") (pin "16") (pinfunction "CSB_16") (pintype "bidirectional"))
    )
    (net (code "100") (name "unconnected-(U3-CTS-Pad3)") (class "Default")
      (node (ref "U3") (pin "3") (pinfunction "CTS_3") (pintype "bidirectional"))
    )
    (net (code "101") (name "unconnected-(U3-GND1-Pad21)") (class "Default")
      (node (ref "U3") (pin "21") (pinfunction "GND1_21") (pintype "bidirectional"))
    )
    (net (code "102") (name "unconnected-(U3-GND2-Pad22)") (class "Default")
      (node (ref "U3") (pin "22") (pinfunction "GND2_22") (pintype "bidirectional"))
    )
    (net (code "103") (name "unconnected-(U3-MISO-Pad18)") (class "Default")
      (node (ref "U3") (pin "18") (pinfunction "MISO_18") (pintype "bidirectional"))
    )
    (net (code "104") (name "unconnected-(U3-MOSI-Pad17)") (class "Default")
      (node (ref "U3") (pin "17") (pinfunction "MOSI_17") (pintype "bidirectional"))
    )
    (net (code "105") (name "unconnected-(U3-NC-Pad14)") (class "Default")
      (node (ref "U3") (pin "14") (pinfunction "NC_14") (pintype "bidirectional"))
    )
    (net (code "106") (name "unconnected-(U3-PCM_CLK-Pad5)") (class "Default")
      (node (ref "U3") (pin "5") (pinfunction "PCM_CLK_5") (pintype "bidirectional"))
    )
    (net (code "107") (name "unconnected-(U3-PCM_IN-Pad7)") (class "Default")
      (node (ref "U3") (pin "7") (pinfunction "PCM_IN_7") (pintype "bidirectional"))
    )
    (net (code "108") (name "unconnected-(U3-PCM_OUT-Pad6)") (class "Default")
      (node (ref "U3") (pin "6") (pinfunction "PCM_OUT_6") (pintype "bidirectional"))
    )
    (net (code "109") (name "unconnected-(U3-PCN_SYNC-Pad8)") (class "Default")
      (node (ref "U3") (pin "8") (pinfunction "PCN_SYNC_8") (pintype "bidirectional"))
    )
    (net (code "110") (name "unconnected-(U3-PIO0-Pad23)") (class "Default")
      (node (ref "U3") (pin "23") (pinfunction "PIO0_23") (pintype "bidirectional"))
    )
    (net (code "111") (name "unconnected-(U3-PIO1-Pad24)") (class "Default")
      (node (ref "U3") (pin "24") (pinfunction "PIO1_24") (pintype "bidirectional"))
    )
    (net (code "112") (name "unconnected-(U3-PIO2-Pad25)") (class "Default")
      (node (ref "U3") (pin "25") (pinfunction "PIO2_25") (pintype "bidirectional"))
    )
    (net (code "113") (name "unconnected-(U3-PIO3-Pad26)") (class "Default")
      (node (ref "U3") (pin "26") (pinfunction "PIO3_26") (pintype "bidirectional"))
    )
    (net (code "114") (name "unconnected-(U3-PIO4-Pad27)") (class "Default")
      (node (ref "U3") (pin "27") (pinfunction "PIO4_27") (pintype "bidirectional"))
    )
    (net (code "115") (name "unconnected-(U3-PIO5-Pad28)") (class "Default")
      (node (ref "U3") (pin "28") (pinfunction "PIO5_28") (pintype "bidirectional"))
    )
    (net (code "116") (name "unconnected-(U3-PIO6-Pad29)") (class "Default")
      (node (ref "U3") (pin "29") (pinfunction "PIO6_29") (pintype "bidirectional"))
    )
    (net (code "117") (name "unconnected-(U3-PIO7-Pad30)") (class "Default")
      (node (ref "U3") (pin "30") (pinfunction "PIO7_30") (pintype "bidirectional"))
    )
    (net (code "118") (name "unconnected-(U3-PIO8-Pad31)") (class "Default")
      (node (ref "U3") (pin "31") (pinfunction "PIO8_31") (pintype "bidirectional"))
    )
    (net (code "119") (name "unconnected-(U3-PIO9-Pad32)") (class "Default")
      (node (ref "U3") (pin "32") (pinfunction "PIO9_32") (pintype "bidirectional"))
    )
    (net (code "120") (name "unconnected-(U3-PIO10-Pad33)") (class "Default")
      (node (ref "U3") (pin "33") (pinfunction "PIO10_33") (pintype "bidirectional"))
    )
    (net (code "121") (name "unconnected-(U3-PIO11-Pad34)") (class "Default")
      (node (ref "U3") (pin "34") (pinfunction "PIO11_34") (pintype "bidirectional"))
    )
    (net (code "122") (name "unconnected-(U3-RST-Pad11)") (class "Default")
      (node (ref "U3") (pin "11") (pinfunction "RST_11") (pintype "bidirectional"))
    )
    (net (code "123") (name "unconnected-(U3-RTS-Pad4)") (class "Default")
      (node (ref "U3") (pin "4") (pinfunction "RTS_4") (pintype "bidirectional"))
    )
    (net (code "124") (name "unconnected-(U3-VBUSD+-Pad20)") (class "Default")
      (node (ref "U3") (pin "20") (pinfunction "VBUSD+_20") (pintype "bidirectional"))
    )
    (net (code "125") (name "unconnected-(U3-VBUSD--Pad15)") (class "Default")
      (node (ref "U3") (pin "15") (pinfunction "VBUSD-_15") (pintype "bidirectional"))
    )
  )
)
